# Pwr.net
KiCad netlist of a schematic drawn in Altium Designer
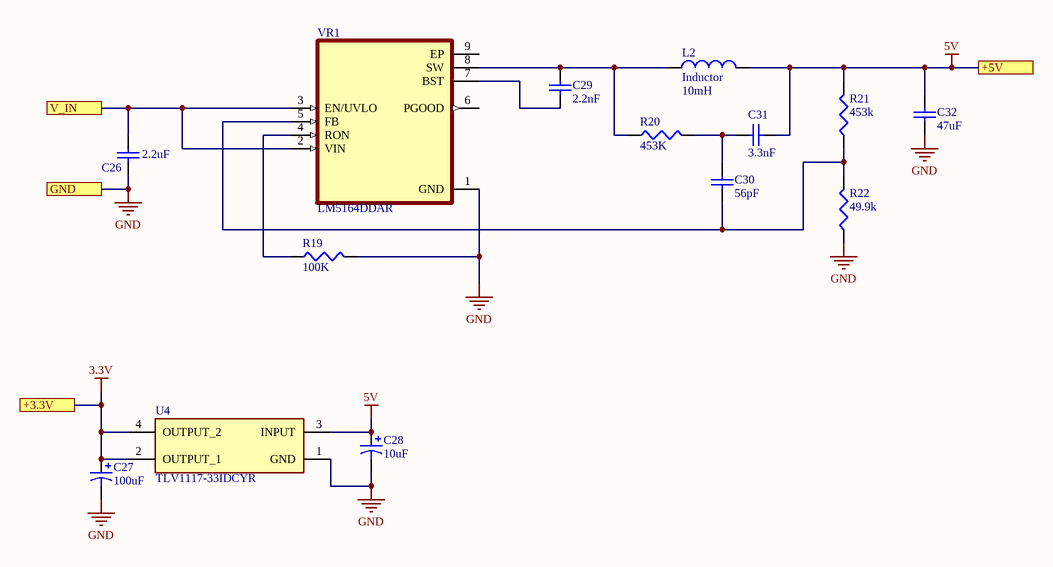
[diagram p0: Pwr.SchDoc]

(export (version "E")
  (design (tool "Eeschema 10.0.6"))
  (components
    (comp (ref "C26")
      (value "2.2uF")
      (footprint "C0805")
      (description "Capacitor")
      (fields (field (name "Comment") "Cap") (field (name "PUBLISHER") "Altium Limited"))
      (libsource (lib "Miscellaneous Devices") (part "Cap"))
    )
    (comp (ref "C27")
      (value "100uF")
      (footprint "CAPAE660X800N")
      (description "Polarized Capacitor (Surface Mount)")
      (fields (field (name "Comment") "Cap Pol3") (field (name "PUBLISHER") "Altium Limited"))
      (libsource (lib "Miscellaneous Devices") (part "Cap Pol3"))
    )
    (comp (ref "C28")
      (value "10uF")
      (footprint "CAPAE660X800N")
      (description "Polarized Capacitor (Surface Mount)")
      (fields (field (name "Comment") "Cap Pol3") (field (name "PUBLISHER") "Altium Limited"))
      (libsource (lib "Miscellaneous Connectors") (part "Cap Pol3"))
    )
    (comp (ref "C29")
      (value "2.2nF")
      (footprint "C0805")
      (description "Capacitor")
      (fields (field (name "Comment") "Cap") (field (name "PUBLISHER") "Altium Limited"))
      (libsource (lib "Miscellaneous Devices") (part "Cap"))
    )
    (comp (ref "C30")
      (value "56pF")
      (footprint "C0805")
      (description "Capacitor")
      (fields (field (name "Comment") "Cap") (field (name "PUBLISHER") "Altium Limited"))
      (libsource (lib "Miscellaneous Devices") (part "Cap"))
    )
    (comp (ref "C31")
      (value "3.3nF")
      (footprint "C0805")
      (description "Capacitor")
      (fields (field (name "Comment") "Cap") (field (name "PUBLISHER") "Altium Limited"))
      (libsource (lib "Miscellaneous Devices") (part "Cap"))
    )
    (comp (ref "C32")
      (value "47uF")
      (footprint "C0805")
      (description "Capacitor")
      (fields (field (name "Comment") "Cap") (field (name "PUBLISHER") "Altium Limited"))
      (libsource (lib "Miscellaneous Devices") (part "Cap"))
    )
    (comp (ref "L2")
      (value "Inductor")
      (footprint "0402-A")
      (fields (field (name "ALTIUM_VALUE") "10mH") (field (name "PUBLISHER") "Altium Limited"))
      (libsource (lib "Miscellaneous Devices") (part "Inductor"))
    )
    (comp (ref "R19")
      (value "100K")
      (footprint "J1-0603")
      (description "Resistor")
      (fields (field (name "Comment") "Res3") (field (name "PUBLISHER") "Altium Limited"))
      (libsource (lib "Miscellaneous Devices") (part "Res3"))
    )
    (comp (ref "R20")
      (value "453K")
      (footprint "J1-0603")
      (description "Resistor")
      (fields (field (name "Comment") "Res3") (field (name "PUBLISHER") "Altium Limited"))
      (libsource (lib "Miscellaneous Devices") (part "Res3"))
    )
    (comp (ref "R21")
      (value "453k")
      (footprint "J1-0603")
      (description "Resistor")
      (fields (field (name "Comment") "Res3") (field (name "PUBLISHER") "Altium Limited"))
      (libsource (lib "Miscellaneous Devices") (part "Res3"))
    )
    (comp (ref "R22")
      (value "49.9k")
      (footprint "J1-0603")
      (description "Resistor")
      (fields (field (name "Comment") "Res3") (field (name "PUBLISHER") "Altium Limited"))
      (libsource (lib "Miscellaneous Devices") (part "Res3"))
    )
    (comp (ref "U4")
      (value "TLV1117-33IDCYR")
      (footprint "Motor Controller:SOT230P700X180-4N")
      (description "Integrated Circuit")
      (fields (field (name "MOUSER PART NUMBER") "595-TLV1117-33IDCYR"))
      (libsource (lib "Motor Controller") (part "TLV1117-33IDCYR"))
    )
    (comp (ref "VR1")
      (value "LM5164DDAR")
      (footprint "VREG_LM5017MR/NOPB")
      (fields (field (name "MF") "Texas Instruments"))
      (libsource (lib "LM5164DDAR") (part "LM5164DDAR"))
    )
  )
  (nets
    (net (code "1") (name "/V_IN") (class "Default")
      (node (ref "C26") (pin "1") (pinfunction "1_1") (pintype "passive"))
      (node (ref "VR1") (pin "2") (pinfunction "VIN_2") (pintype "input"))
      (node (ref "VR1") (pin "3") (pinfunction "EN/UVLO_3") (pintype "input"))
    )
    (net (code "2") (name "3.3V") (class "Default")
      (node (ref "C27") (pin "1") (pinfunction "1_1") (pintype "passive"))
      (node (ref "U4") (pin "2") (pinfunction "OUTPUT_1_2") (pintype "passive"))
      (node (ref "U4") (pin "4") (pinfunction "OUTPUT_2_4") (pintype "passive"))
    )
    (net (code "3") (name "5V") (class "Default")
      (node (ref "C28") (pin "1") (pinfunction "1_1") (pintype "passive"))
      (node (ref "C31") (pin "1") (pinfunction "1_1") (pintype "passive"))
      (node (ref "C32") (pin "1") (pinfunction "1_1") (pintype "passive"))
      (node (ref "L2") (pin "2") (pinfunction "2_2") (pintype "passive"))
      (node (ref "R21") (pin "2") (pinfunction "2_2") (pintype "passive"))
      (node (ref "U4") (pin "3") (pinfunction "INPUT_3") (pintype "passive"))
    )
    (net (code "4") (name "GND") (class "Default")
      (node (ref "C26") (pin "2") (pinfunction "2_2") (pintype "passive"))
      (node (ref "C27") (pin "2") (pinfunction "2_2") (pintype "passive"))
      (node (ref "C28") (pin "2") (pinfunction "2_2") (pintype "passive"))
      (node (ref "C32") (pin "2") (pinfunction "2_2") (pintype "passive"))
      (node (ref "R19") (pin "2") (pinfunction "2_2") (pintype "passive"))
      (node (ref "R22") (pin "1") (pinfunction "1_1") (pintype "passive"))
      (node (ref "U4") (pin "1") (pinfunction "GND_1") (pintype "passive"))
      (node (ref "VR1") (pin "1") (pinfunction "GND_1") (pintype "power_in"))
    )
    (net (code "5") (name "Net-(C30-Pad1)") (class "Default")
      (node (ref "C30") (pin "1") (pinfunction "1_1") (pintype "passive"))
      (node (ref "C31") (pin "2") (pinfunction "2_2") (pintype "passive"))
      (node (ref "R20") (pin "2") (pinfunction "2_2") (pintype "passive"))
    )
    (net (code "6") (name "Net-(VR1-BST)") (class "Default")
      (node (ref "C29") (pin "1") (pinfunction "1_1") (pintype "passive"))
      (node (ref "VR1") (pin "7") (pinfunction "BST_7") (pintype "power_in"))
    )
    (net (code "7") (name "Net-(VR1-FB)") (class "Default")
      (node (ref "C30") (pin "2") (pinfunction "2_2") (pintype "passive"))
      (node (ref "R21") (pin "1") (pinfunction "1_1") (pintype "passive"))
      (node (ref "R22") (pin "2") (pinfunction "2_2") (pintype "passive"))
      (node (ref "VR1") (pin "5") (pinfunction "FB_5") (pintype "input"))
    )
    (net (code "8") (name "Net-(VR1-RON)") (class "Default")
      (node (ref "R19") (pin "1") (pinfunction "1_1") (pintype "passive"))
      (node (ref "VR1") (pin "4") (pinfunction "RON_4") (pintype "input"))
    )
    (net (code "9") (name "Net-(VR1-SW)") (class "Default")
      (node (ref "C29") (pin "2") (pinfunction "2_2") (pintype "passive"))
      (node (ref "L2") (pin "1") (pinfunction "1_1") (pintype "passive"))
      (node (ref "R20") (pin "1") (pinfunction "1_1") (pintype "passive"))
      (node (ref "VR1") (pin "8") (pinfunction "SW_8") (pintype "power_in"))
    )
    (net (code "10") (name "unconnected-(VR1-EP-Pad9)") (class "Default")
      (node (ref "VR1") (pin "9") (pinfunction "EP_9") (pintype "power_in"))
    )
    (net (code "11") (name "unconnected-(VR1-PGOOD-Pad6)") (class "Default")
      (node (ref "VR1") (pin "6") (pinfunction "PGOOD_6") (pintype "output"))
    )
  )
)
